# MLS01-TG000-C09.net
KiCad netlist of a schematic drawn in EAGLE
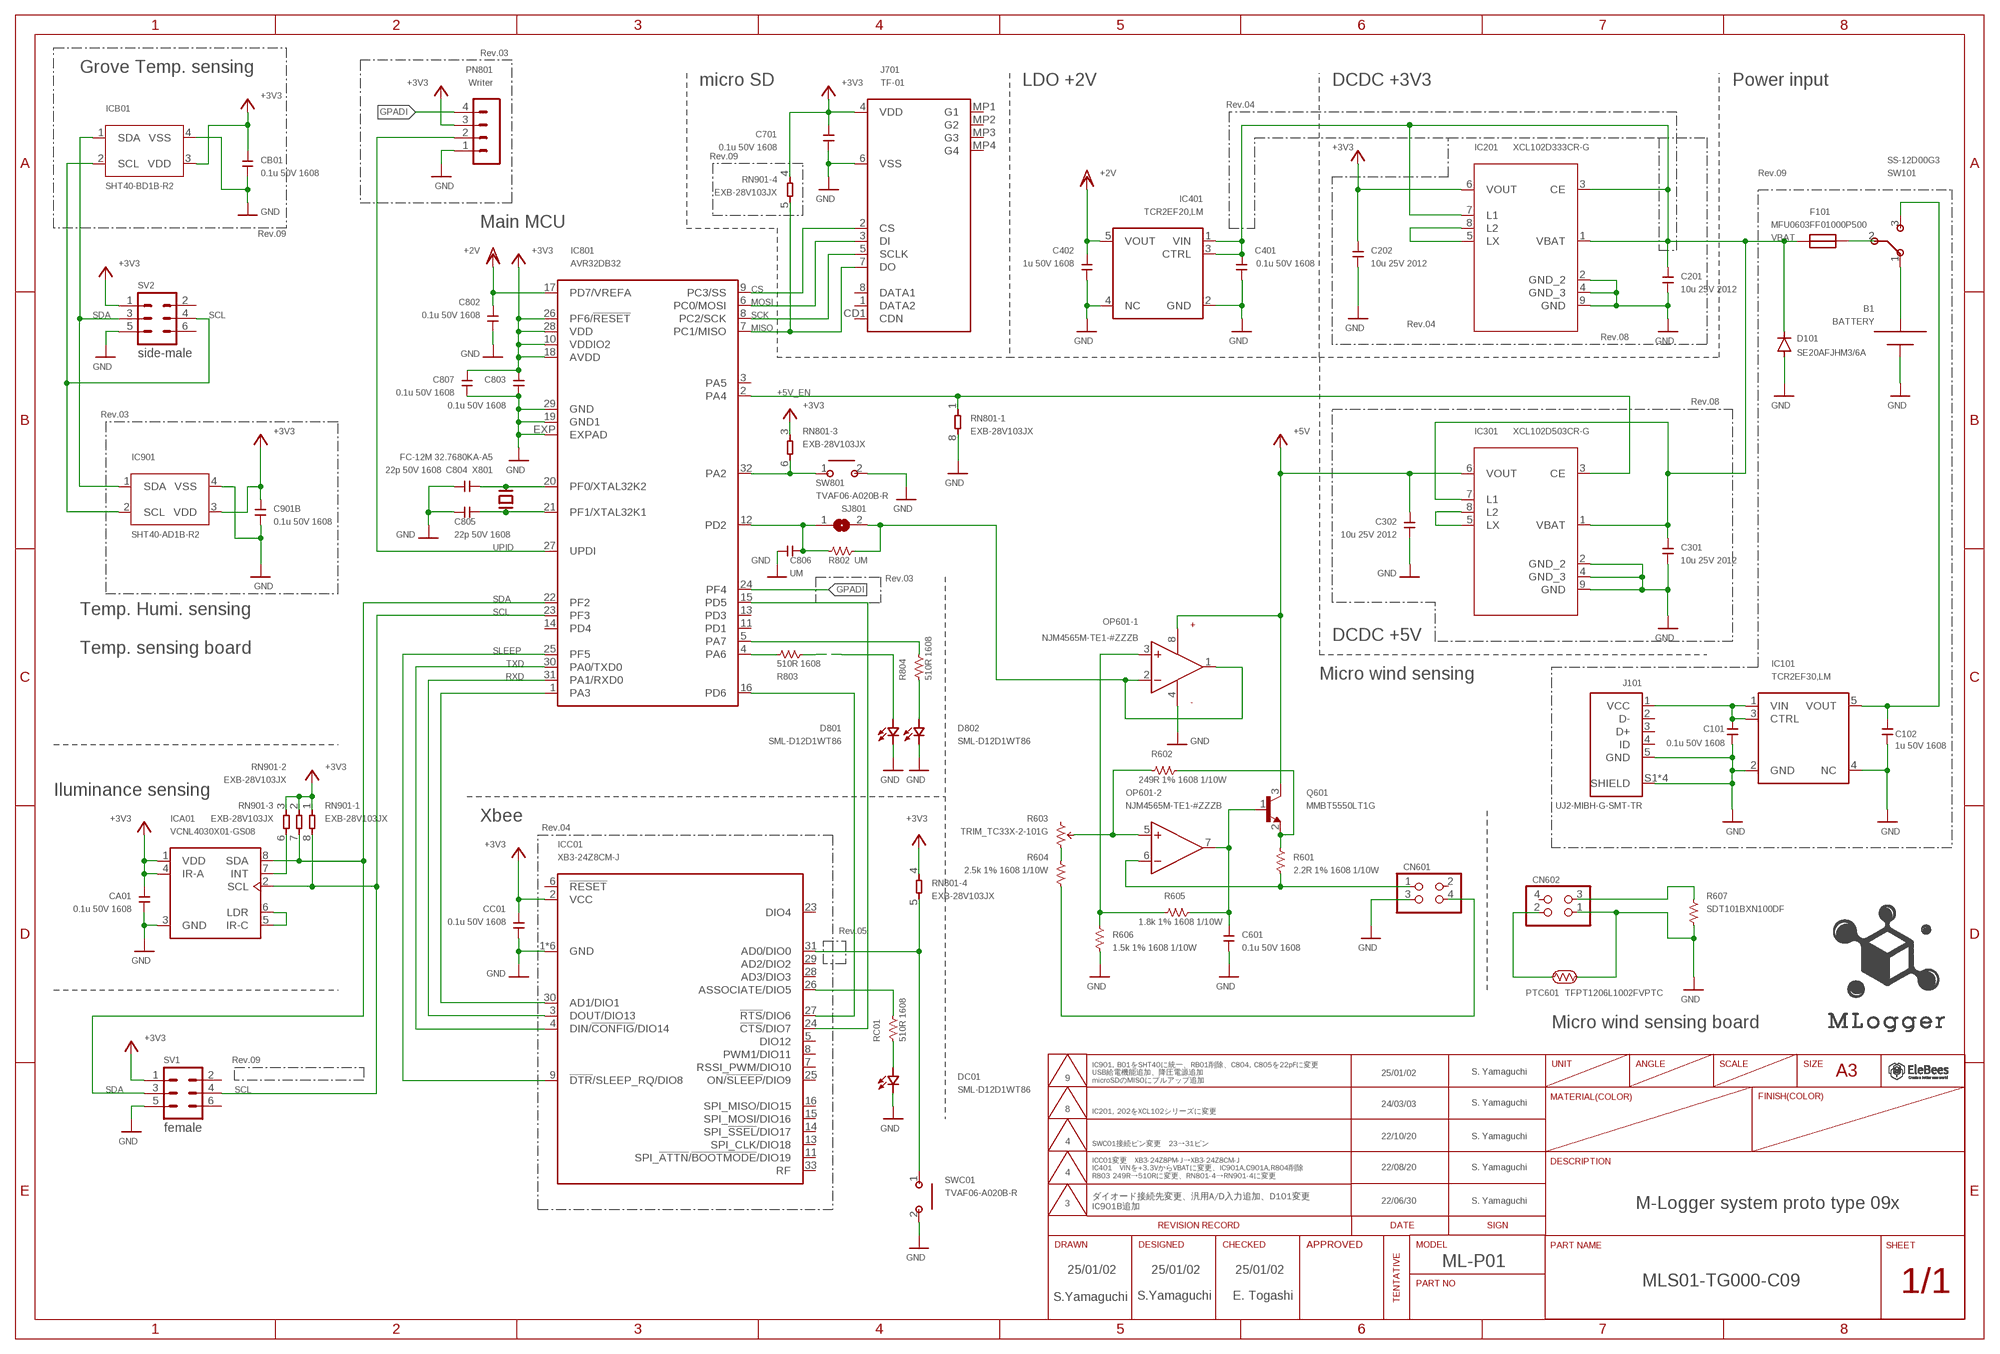
[diagram p0: schematic, sheet 1]

(export (version "E")
  (design (tool "Eeschema 10.0.6"))
  (components
    (comp (ref "B1")
      (value "BATTERY")
      (footprint "eagle-import:PAD")
      (libsource (lib "eagle-import") (part "BATTERY"))
    )
    (comp (ref "C101")
      (value "0.1u 50V 1608")
      (footprint "eagle-import:C-1608_0603")
      (libsource (lib "eagle-import") (part "CL10A105KP8NNNC"))
    )
    (comp (ref "C102")
      (value "1u 50V 1608")
      (footprint "eagle-import:C-1608_0603")
      (libsource (lib "eagle-import") (part "CL10A105KP8NNNC"))
    )
    (comp (ref "C201")
      (value "10u 25V 2012")
      (footprint "eagle-import:C-2012_0805")
      (libsource (lib "eagle-import") (part "CL21B105KBFNNNG"))
    )
    (comp (ref "C202")
      (value "10u 25V 2012")
      (footprint "eagle-import:C-2012_0805")
      (libsource (lib "eagle-import") (part "CL21B105KBFNNNG"))
    )
    (comp (ref "C301")
      (value "10u 25V 2012")
      (footprint "eagle-import:C-2012_0805")
      (libsource (lib "eagle-import") (part "CL21B105KBFNNNG"))
    )
    (comp (ref "C302")
      (value "10u 25V 2012")
      (footprint "eagle-import:C-2012_0805")
      (libsource (lib "eagle-import") (part "CL21B105KBFNNNG"))
    )
    (comp (ref "C401")
      (value "0.1u 50V 1608")
      (footprint "eagle-import:C-1608_0603")
      (libsource (lib "eagle-import") (part "CL10A105KP8NNNC"))
    )
    (comp (ref "C402")
      (value "1u 50V 1608")
      (footprint "eagle-import:C-1608_0603")
      (libsource (lib "eagle-import") (part "CL10A105KP8NNNC"))
    )
    (comp (ref "C601")
      (value "0.1u 50V 1608")
      (footprint "eagle-import:C-1608_0603")
      (libsource (lib "eagle-import") (part "CL10A105KP8NNNC"))
    )
    (comp (ref "C701")
      (value "0.1u 50V 1608")
      (footprint "eagle-import:C-1608_0603")
      (libsource (lib "eagle-import") (part "CL10A105KP8NNNC"))
    )
    (comp (ref "C802")
      (value "0.1u 50V 1608")
      (footprint "eagle-import:C-1608_0603")
      (libsource (lib "eagle-import") (part "CL10A105KP8NNNC"))
    )
    (comp (ref "C803")
      (value "0.1u 50V 1608")
      (footprint "eagle-import:C-1608_0603")
      (libsource (lib "eagle-import") (part "CL10A105KP8NNNC"))
    )
    (comp (ref "C804")
      (value "22p 50V 1608")
      (footprint "eagle-import:C-1608_0603")
      (libsource (lib "eagle-import") (part "CL10A105KP8NNNC"))
    )
    (comp (ref "C805")
      (value "22p 50V 1608")
      (footprint "eagle-import:C-1608_0603")
      (libsource (lib "eagle-import") (part "CL10A105KP8NNNC"))
    )
    (comp (ref "C806")
      (value "UM")
      (footprint "eagle-import:C-1608_0603")
      (libsource (lib "eagle-import") (part "CL10A105KP8NNNC"))
    )
    (comp (ref "C807")
      (value "0.1u 50V 1608")
      (footprint "eagle-import:C-1608_0603")
      (libsource (lib "eagle-import") (part "CL10A105KP8NNNC"))
    )
    (comp (ref "C901B")
      (value "0.1u 50V 1608")
      (footprint "eagle-import:C-1608_0603")
      (libsource (lib "eagle-import") (part "CL10A105KP8NNNC"))
    )
    (comp (ref "CA01")
      (value "0.1u 50V 1608")
      (footprint "eagle-import:C-1608_0603")
      (libsource (lib "eagle-import") (part "CL10A105KP8NNNC"))
    )
    (comp (ref "CB01")
      (value "0.1u 50V 1608")
      (footprint "eagle-import:C-1608_0603")
      (libsource (lib "eagle-import") (part "CL10A105KP8NNNC"))
    )
    (comp (ref "CC01")
      (value "0.1u 50V 1608")
      (footprint "eagle-import:C-1608_0603")
      (libsource (lib "eagle-import") (part "CL10A105KP8NNNC"))
    )
    (comp (ref "CN601")
      (value "PINHD-2X2")
      (footprint "eagle-import:2X02")
      (libsource (lib "eagle-import") (part "PINHD-2X2"))
    )
    (comp (ref "CN602")
      (value "PINHD-2X2")
      (footprint "eagle-import:2X02")
      (libsource (lib "eagle-import") (part "PINHD-2X2"))
    )
    (comp (ref "D101")
      (value "SE20AFJHM3/6A")
      (footprint "eagle-import:SODFL5629X125N")
      (libsource (lib "eagle-import") (part "GS2JFL-TP"))
    )
    (comp (ref "D801")
      (value "SML-D12D1WT86")
      (footprint "eagle-import:SMD-1608")
      (libsource (lib "eagle-import") (part "SML-D12D1WT86"))
    )
    (comp (ref "D802")
      (value "SML-D12D1WT86")
      (footprint "eagle-import:SMD-1608")
      (libsource (lib "eagle-import") (part "SML-D12D1WT86"))
    )
    (comp (ref "DC01")
      (value "SML-D12D1WT86")
      (footprint "eagle-import:SMD-1608")
      (libsource (lib "eagle-import") (part "SML-D12D1WT86"))
    )
    (comp (ref "F101")
      (value "MFU0603FF01000P500")
      (footprint "eagle-import:FUSC1608X60N")
      (libsource (lib "eagle-import") (part "MFU0603FF01000P500"))
    )
    (comp (ref "IC101")
      (value "TCR2EF30,LM")
      (footprint "eagle-import:SOT23-5L")
      (libsource (lib "eagle-import") (part "TCR2EF20,LM"))
    )
    (comp (ref "IC201")
      (value "XCL102D333CR-G")
      (footprint "eagle-import:CL-2025-02_TOR")
      (fields
        (field (name "MANUFACTURER_PART_NUMBER") "XCL102D503CR-G")
        (field (name "COPYRIGHT") "Copyright (C) 2021 Accelerated Designs. All rights reserved")
      )
      (libsource (lib "eagle-import") (part "XCL102D503CR-GCL-2025-02_TOR"))
    )
    (comp (ref "IC301")
      (value "XCL102D503CR-G")
      (footprint "eagle-import:CL-2025-02_TOR")
      (fields (field (name "COPYRIGHT") "Copyright (C) 2021 Accelerated Designs. All rights reserved"))
      (libsource (lib "eagle-import") (part "XCL102D503CR-GCL-2025-02_TOR"))
    )
    (comp (ref "IC401")
      (value "TCR2EF20,LM")
      (footprint "eagle-import:SOT23-5L")
      (libsource (lib "eagle-import") (part "TCR2EF20,LM"))
    )
    (comp (ref "IC801")
      (value "AVR32DB32")
      (footprint "eagle-import:HVQFN32")
      (libsource (lib "eagle-import") (part "AVR32DB32"))
    )
    (comp (ref "IC901")
      (value "SHT40-AD1B-R2")
      (footprint "eagle-import:SHT41")
      (libsource (lib "eagle-import") (part "SHT41"))
    )
    (comp (ref "ICA01")
      (value "VCNL4030X01-GS08")
      (footprint "eagle-import:VISHAY_VCNL4030X01-GS08")
      (fields (field (name "MF") "Vishay"))
      (libsource (lib "eagle-import") (part "VCNL4030X01-GS08"))
    )
    (comp (ref "ICB01")
      (value "SHT40-BD1B-R2")
      (footprint "eagle-import:SHT41")
      (libsource (lib "eagle-import") (part "SHT41"))
    )
    (comp (ref "ICC01")
      (value "XB3-24Z8CM-J")
      (footprint "eagle-import:XCVR_XB3-24Z8CM-J")
      (fields (field (name "MF") "Digi International"))
      (libsource (lib "eagle-import") (part "XB3-24Z8CM-J"))
    )
    (comp (ref "J101")
      (value "UJ2-MIBH-G-SMT-TR")
      (footprint "eagle-import:CUI_UJ2-MIBH-G-SMT-TR")
      (fields (field (name "MANUFACTURER") "CUI"))
      (libsource (lib "eagle-import") (part "UJ2-MIBH-G-SMT-TR"))
    )
    (comp (ref "J701")
      (value "TF-01")
      (footprint "eagle-import:TF-01A")
      (libsource (lib "eagle-import") (part "TF-01"))
    )
    (comp (ref "OP601")
      (value "NJM4565M-TE1-#ZZZB")
      (footprint "eagle-import:SOIC127P680X175-8N")
      (libsource (lib "eagle-import") (part "NJM4565M-TE1-#ZZZB"))
    )
    (comp (ref "PN801")
      (value "Writer")
      (footprint "eagle-import:MA04-1")
      (libsource (lib "eagle-import") (part "MA04-1"))
    )
    (comp (ref "PTC601")
      (value "TFPT1206L1002FVPTC")
      (footprint "eagle-import:C1206")
      (libsource (lib "eagle-import") (part "TFPT1206L1002FVPTC"))
    )
    (comp (ref "Q601")
      (value "MMBT5550LT1G")
      (footprint "eagle-import:SOT95P237X111-3N")
      (libsource (lib "eagle-import") (part "MMBT5550LT1G"))
    )
    (comp (ref "R601")
      (value "2.2R 1% 1608 1/10W")
      (footprint "eagle-import:R-1608_0603")
      (libsource (lib "eagle-import") (part "R-1608"))
    )
    (comp (ref "R602")
      (value "249R 1% 1608 1/10W")
      (footprint "eagle-import:R-1608_0603")
      (libsource (lib "eagle-import") (part "R-1608"))
    )
    (comp (ref "R603")
      (value "TRIM_TC33X-2-101G")
      (footprint "eagle-import:TRIM_TC33X-2-101G")
      (libsource (lib "eagle-import") (part "TRIM_TC33X-2-101G"))
    )
    (comp (ref "R604")
      (value "2.5k 1% 1608 1/10W")
      (footprint "eagle-import:R-1608_0603")
      (libsource (lib "eagle-import") (part "R-1608"))
    )
    (comp (ref "R605")
      (value "1.8k 1% 1608 1/10W")
      (footprint "eagle-import:R-1608_0603")
      (libsource (lib "eagle-import") (part "R-1608"))
    )
    (comp (ref "R606")
      (value "1.5k 1% 1608 1/10W")
      (footprint "eagle-import:R-1608_0603")
      (libsource (lib "eagle-import") (part "R-1608"))
    )
    (comp (ref "R607")
      (value "SDT101BXN100DF")
      (footprint "eagle-import:SDT101BXN100DF")
      (libsource (lib "eagle-import") (part "SDT101BXN100DF"))
    )
    (comp (ref "R802")
      (value "UM")
      (footprint "eagle-import:R-1608_0603")
      (libsource (lib "eagle-import") (part "R-1608"))
    )
    (comp (ref "R803")
      (value "510R 1608")
      (footprint "eagle-import:R-1608_0603")
      (libsource (lib "eagle-import") (part "R-1608"))
    )
    (comp (ref "R804")
      (value "510R 1608")
      (footprint "eagle-import:R-1608_0603")
      (libsource (lib "eagle-import") (part "R-1608"))
    )
    (comp (ref "RC01")
      (value "510R 1608")
      (footprint "eagle-import:R-1608_0603")
      (libsource (lib "eagle-import") (part "R-1608"))
    )
    (comp (ref "RN801")
      (value "EXB-28V103JX")
      (footprint "eagle-import:RESCAXS50P200X100X45-8N")
      (libsource (lib "eagle-import") (part "EXB-28V103JX"))
    )
    (comp (ref "RN901")
      (value "EXB-28V103JX")
      (footprint "eagle-import:RESCAXS50P200X100X45-8N")
      (libsource (lib "eagle-import") (part "EXB-28V103JX"))
    )
    (comp (ref "SJ801")
      (value "SJ")
      (footprint "eagle-import:SJ")
      (libsource (lib "eagle-import") (part "SJ"))
    )
    (comp (ref "SV1")
      (value "female")
      (footprint "eagle-import:MA03-2-FEMALE")
      (libsource (lib "eagle-import") (part "MA03-2-FEMALE"))
    )
    (comp (ref "SV2")
      (value "side-male")
      (footprint "eagle-import:MA03-2-SIDE-MALE")
      (libsource (lib "eagle-import") (part "MA03-2-SIDE-MALE"))
    )
    (comp (ref "SW101")
      (value "SS-12D00G3")
      (footprint "eagle-import:SS-12D00G3")
      (libsource (lib "eagle-import") (part "SS-12D00G3"))
    )
    (comp (ref "SW801")
      (value "TVAF06-A020B-R")
      (footprint "eagle-import:TVAF06-A020B-R")
      (libsource (lib "eagle-import") (part "TVAF06-A020B-R"))
    )
    (comp (ref "SWC01")
      (value "TVAF06-A020B-R")
      (footprint "eagle-import:TVAF06-A020B-R")
      (libsource (lib "eagle-import") (part "TVAF06-A020B-R"))
    )
    (comp (ref "U$4")
      (value "ELEBEES_SMALL")
      (footprint "eagle-import:ELEBEES_SMALL")
      (libsource (lib "eagle-import") (part "ELEBEES_SMALL"))
    )
    (comp (ref "X801")
      (value "FC-12M 32.7680KA-A5")
      (footprint "eagle-import:X2-SMD-L2.0X1.2X0.55MM")
      (fields (field (name "MF") "EPSON") (field (name "MP") "FC-12M"))
      (libsource (lib "eagle-import") (part "SMD-CRYSTAL-32.768KHZ-12.5PF-20PPM-90K(2P-L2.0X1.2MM)"))
    )
  )
  (nets
    (net (code "1") (name "+2V") (class "Default")
      (node (ref "C402") (pin "P$1") (pinfunction "1_P$1") (pintype "passive"))
      (node (ref "C802") (pin "P$1") (pinfunction "1_P$1") (pintype "passive"))
      (node (ref "IC401") (pin "5") (pinfunction "VOUT_5") (pintype "bidirectional"))
      (node (ref "IC801") (pin "17") (pinfunction "PD7/VREFA_17") (pintype "bidirectional"))
    )
    (net (code "2") (name "+3V3") (class "Default")
      (node (ref "C202") (pin "P$2") (pinfunction "2_P$2") (pintype "passive"))
      (node (ref "C701") (pin "P$1") (pinfunction "1_P$1") (pintype "passive"))
      (node (ref "C803") (pin "P$1") (pinfunction "1_P$1") (pintype "passive"))
      (node (ref "C807") (pin "P$1") (pinfunction "1_P$1") (pintype "passive"))
      (node (ref "C901B") (pin "P$1") (pinfunction "1_P$1") (pintype "passive"))
      (node (ref "CA01") (pin "P$1") (pinfunction "1_P$1") (pintype "passive"))
      (node (ref "CB01") (pin "P$1") (pinfunction "1_P$1") (pintype "passive"))
      (node (ref "CC01") (pin "P$1") (pinfunction "1_P$1") (pintype "passive"))
      (node (ref "IC201") (pin "6") (pinfunction "VOUT_6") (pintype "output"))
      (node (ref "IC801") (pin "10") (pinfunction "VDDIO2_10") (pintype "bidirectional"))
      (node (ref "IC801") (pin "18") (pinfunction "AVDD_18") (pintype "bidirectional"))
      (node (ref "IC801") (pin "26") (pinfunction "PF6/~{RESET}_26") (pintype "bidirectional"))
      (node (ref "IC801") (pin "28") (pinfunction "VDD_28") (pintype "bidirectional"))
      (node (ref "IC901") (pin "3") (pinfunction "VDD_3") (pintype "bidirectional"))
      (node (ref "ICA01") (pin "1") (pinfunction "VDD_1") (pintype "power_in"))
      (node (ref "ICA01") (pin "4") (pinfunction "IR-A_4") (pintype "input"))
      (node (ref "ICB01") (pin "3") (pinfunction "VDD_3") (pintype "bidirectional"))
      (node (ref "ICC01") (pin "2") (pinfunction "VCC_2") (pintype "power_in"))
      (node (ref "J701") (pin "4") (pinfunction "VDD_4") (pintype "bidirectional"))
      (node (ref "PN801") (pin "3") (pinfunction "3_3") (pintype "passive"))
      (node (ref "RN801") (pin "3") (pinfunction "1_3") (pintype "passive"))
      (node (ref "RN801") (pin "4") (pinfunction "1_4") (pintype "passive"))
      (node (ref "RN901") (pin "1") (pinfunction "1_1") (pintype "passive"))
      (node (ref "RN901") (pin "2") (pinfunction "1_2") (pintype "passive"))
      (node (ref "RN901") (pin "3") (pinfunction "1_3") (pintype "passive"))
      (node (ref "RN901") (pin "4") (pinfunction "1_4") (pintype "passive"))
      (node (ref "SV1") (pin "1") (pinfunction "1_1") (pintype "passive"))
      (node (ref "SV2") (pin "1") (pinfunction "1_1") (pintype "passive"))
    )
    (net (code "3") (name "+5V") (class "Default")
      (node (ref "C302") (pin "P$2") (pinfunction "2_P$2") (pintype "passive"))
      (node (ref "IC301") (pin "6") (pinfunction "VOUT_6") (pintype "output"))
      (node (ref "OP601") (pin "8") (pinfunction "V+_8") (pintype "power_in"))
      (node (ref "Q601") (pin "3") (pinfunction "C_3") (pintype "passive"))
    )
    (net (code "4") (name "/+5V_EN") (class "Default")
      (node (ref "IC301") (pin "3") (pinfunction "CE_3") (pintype "input"))
      (node (ref "IC801") (pin "2") (pinfunction "PA4_2") (pintype "bidirectional"))
      (node (ref "RN801") (pin "1") (pinfunction "1_1") (pintype "passive"))
    )
    (net (code "5") (name "/CS") (class "Default")
      (node (ref "IC801") (pin "9") (pinfunction "PC3/SS_9") (pintype "bidirectional"))
      (node (ref "J701") (pin "2") (pinfunction "CS_2") (pintype "bidirectional"))
    )
    (net (code "6") (name "/MISO") (class "Default")
      (node (ref "IC801") (pin "7") (pinfunction "PC1/MISO_7") (pintype "bidirectional"))
      (node (ref "J701") (pin "7") (pinfunction "DO_7") (pintype "bidirectional"))
      (node (ref "RN901") (pin "5") (pinfunction "2_5") (pintype "passive"))
    )
    (net (code "7") (name "/MOSI") (class "Default")
      (node (ref "IC801") (pin "6") (pinfunction "PC0/MOSI_6") (pintype "bidirectional"))
      (node (ref "J701") (pin "3") (pinfunction "DI_3") (pintype "bidirectional"))
    )
    (net (code "8") (name "/N$3") (class "Default")
      (node (ref "CN601") (pin "4") (pinfunction "4_4") (pintype "passive"))
      (node (ref "CN602") (pin "2") (pinfunction "2_2") (pintype "passive"))
      (node (ref "PTC601") (pin "2") (pinfunction "2_2") (pintype "passive"))
      (node (ref "R604") (pin "1") (pinfunction "1_1") (pintype "passive"))
    )
    (net (code "9") (name "/N$20") (class "Default")
      (node (ref "CN601") (pin "1") (pinfunction "1_1") (pintype "passive"))
      (node (ref "CN602") (pin "3") (pinfunction "3_3") (pintype "passive"))
      (node (ref "OP601") (pin "6") (pinfunction "-IN_6") (pintype "input"))
      (node (ref "R601") (pin "1") (pinfunction "1_1") (pintype "passive"))
      (node (ref "R607") (pin "2") (pinfunction "2_2") (pintype "passive"))
    )
    (net (code "10") (name "/RXD") (class "Default")
      (node (ref "IC801") (pin "31") (pinfunction "PA1/RXD0_31") (pintype "bidirectional"))
      (node (ref "ICC01") (pin "3") (pinfunction "DOUT/DIO13_3") (pintype "bidirectional"))
    )
    (net (code "11") (name "/SCK") (class "Default")
      (node (ref "IC801") (pin "8") (pinfunction "PC2/SCK_8") (pintype "bidirectional"))
      (node (ref "J701") (pin "5") (pinfunction "SCLK_5") (pintype "bidirectional"))
    )
    (net (code "12") (name "/SCL") (class "Default")
      (node (ref "IC801") (pin "23") (pinfunction "PF3_23") (pintype "bidirectional"))
      (node (ref "IC901") (pin "2") (pinfunction "SCL_2") (pintype "bidirectional"))
      (node (ref "ICA01") (pin "2") (pinfunction "SCL_2") (pintype "input"))
      (node (ref "ICB01") (pin "2") (pinfunction "SCL_2") (pintype "bidirectional"))
      (node (ref "RN901") (pin "8") (pinfunction "2_8") (pintype "passive"))
      (node (ref "SV1") (pin "4") (pinfunction "4_4") (pintype "passive"))
      (node (ref "SV2") (pin "4") (pinfunction "4_4") (pintype "passive"))
    )
    (net (code "13") (name "/SDA") (class "Default")
      (node (ref "IC801") (pin "22") (pinfunction "PF2_22") (pintype "bidirectional"))
      (node (ref "IC901") (pin "1") (pinfunction "SDA_1") (pintype "bidirectional"))
      (node (ref "ICA01") (pin "8") (pinfunction "SDA_8") (pintype "bidirectional"))
      (node (ref "ICB01") (pin "1") (pinfunction "SDA_1") (pintype "bidirectional"))
      (node (ref "RN901") (pin "7") (pinfunction "2_7") (pintype "passive"))
      (node (ref "SV1") (pin "3") (pinfunction "3_3") (pintype "passive"))
      (node (ref "SV2") (pin "3") (pinfunction "3_3") (pintype "passive"))
    )
    (net (code "14") (name "/SLEEP") (class "Default")
      (node (ref "IC801") (pin "25") (pinfunction "PF5_25") (pintype "bidirectional"))
      (node (ref "ICC01") (pin "9") (pinfunction "~{DTR}/SLEEP_RQ/DIO8_9") (pintype "bidirectional"))
    )
    (net (code "15") (name "/TXD") (class "Default")
      (node (ref "IC801") (pin "30") (pinfunction "PA0/TXD0_30") (pintype "bidirectional"))
      (node (ref "ICC01") (pin "4") (pinfunction "DIN/~{CONFIG}/DIO14_4") (pintype "bidirectional"))
    )
    (net (code "16") (name "/UPID") (class "Default")
      (node (ref "IC801") (pin "27") (pinfunction "UPDI_27") (pintype "bidirectional"))
      (node (ref "PN801") (pin "2") (pinfunction "2_2") (pintype "passive"))
    )
    (net (code "17") (name "/VBAT") (class "Default")
      (node (ref "C201") (pin "P$2") (pinfunction "2_P$2") (pintype "passive"))
      (node (ref "C301") (pin "P$2") (pinfunction "2_P$2") (pintype "passive"))
      (node (ref "C401") (pin "P$1") (pinfunction "1_P$1") (pintype "passive"))
      (node (ref "D101") (pin "1") (pinfunction "C_1") (pintype "passive"))
      (node (ref "F101") (pin "2") (pinfunction "2_2") (pintype "bidirectional"))
      (node (ref "IC201") (pin "1") (pinfunction "VBAT_1") (pintype "power_in"))
      (node (ref "IC201") (pin "3") (pinfunction "CE_3") (pintype "input"))
      (node (ref "IC201") (pin "7") (pinfunction "L1_7") (pintype "bidirectional"))
      (node (ref "IC301") (pin "1") (pinfunction "VBAT_1") (pintype "power_in"))
      (node (ref "IC301") (pin "7") (pinfunction "L1_7") (pintype "bidirectional"))
      (node (ref "IC401") (pin "1") (pinfunction "VIN_1") (pintype "bidirectional"))
      (node (ref "IC401") (pin "3") (pinfunction "CTRL_3") (pintype "bidirectional"))
    )
    (net (code "18") (name "GND") (class "Default")
      (node (ref "B1") (pin "2") (pinfunction "-_2") (pintype "bidirectional"))
      (node (ref "C101") (pin "P$2") (pinfunction "2_P$2") (pintype "passive"))
      (node (ref "C102") (pin "P$2") (pinfunction "2_P$2") (pintype "passive"))
      (node (ref "C201") (pin "P$1") (pinfunction "1_P$1") (pintype "passive"))
      (node (ref "C202") (pin "P$1") (pinfunction "1_P$1") (pintype "passive"))
      (node (ref "C301") (pin "P$1") (pinfunction "1_P$1") (pintype "passive"))
      (node (ref "C302") (pin "P$1") (pinfunction "1_P$1") (pintype "passive"))
      (node (ref "C401") (pin "P$2") (pinfunction "2_P$2") (pintype "passive"))
      (node (ref "C402") (pin "P$2") (pinfunction "2_P$2") (pintype "passive"))
      (node (ref "C601") (pin "P$2") (pinfunction "2_P$2") (pintype "passive"))
      (node (ref "C701") (pin "P$2") (pinfunction "2_P$2") (pintype "passive"))
      (node (ref "C802") (pin "P$2") (pinfunction "2_P$2") (pintype "passive"))
      (node (ref "C803") (pin "P$2") (pinfunction "2_P$2") (pintype "passive"))
      (node (ref "C804") (pin "P$2") (pinfunction "2_P$2") (pintype "passive"))
      (node (ref "C805") (pin "P$2") (pinfunction "2_P$2") (pintype "passive"))
      (node (ref "C806") (pin "P$2") (pinfunction "2_P$2") (pintype "passive"))
      (node (ref "C807") (pin "P$2") (pinfunction "2_P$2") (pintype "passive"))
      (node (ref "C901B") (pin "P$2") (pinfunction "2_P$2") (pintype "passive"))
      (node (ref "CA01") (pin "P$2") (pinfunction "2_P$2") (pintype "passive"))
      (node (ref "CB01") (pin "P$2") (pinfunction "2_P$2") (pintype "passive"))
      (node (ref "CC01") (pin "P$2") (pinfunction "2_P$2") (pintype "passive"))
      (node (ref "CN601") (pin "3") (pinfunction "3_3") (pintype "passive"))
      (node (ref "CN602") (pin "1") (pinfunction "1_1") (pintype "passive"))
      (node (ref "D101") (pin "2") (pinfunction "A_2") (pintype "passive"))
      (node (ref "D801") (pin "2") (pinfunction "C_2") (pintype "passive"))
      (node (ref "D802") (pin "2") (pinfunction "C_2") (pintype "passive"))
      (node (ref "DC01") (pin "2") (pinfunction "C_2") (pintype "passive"))
      (node (ref "IC101") (pin "2") (pinfunction "GND_2") (pintype "bidirectional"))
      (node (ref "IC101") (pin "4") (pinfunction "NC_4") (pintype "bidirectional"))
      (node (ref "IC201") (pin "2") (pinfunction "GND_2_2") (pintype "passive"))
      (node (ref "IC201") (pin "4") (pinfunction "GND_3_4") (pintype "passive"))
      (node (ref "IC201") (pin "9") (pinfunction "GND_9") (pintype "passive"))
      (node (ref "IC301") (pin "2") (pinfunction "GND_2_2") (pintype "passive"))
      (node (ref "IC301") (pin "4") (pinfunction "GND_3_4") (pintype "passive"))
      (node (ref "IC301") (pin "9") (pinfunction "GND_9") (pintype "passive"))
      (node (ref "IC401") (pin "2") (pinfunction "GND_2") (pintype "bidirectional"))
      (node (ref "IC401") (pin "4") (pinfunction "NC_4") (pintype "bidirectional"))
      (node (ref "IC801") (pin "19") (pinfunction "GND1_19") (pintype "bidirectional"))
      (node (ref "IC801") (pin "29") (pinfunction "GND_29") (pintype "bidirectional"))
      (node (ref "IC801") (pin "EXP") (pinfunction "EXPAD_EXP") (pintype "bidirectional"))
      (node (ref "IC901") (pin "4") (pinfunction "VSS_4") (pintype "bidirectional"))
      (node (ref "ICA01") (pin "3") (pinfunction "GND_3") (pintype "power_in"))
      (node (ref "ICB01") (pin "4") (pinfunction "VSS_4") (pintype "bidirectional"))
      (node (ref "ICC01") (pin "1") (pinfunction "GND_1") (pintype "power_in"))
      (node (ref "ICC01") (pin "10") (pinfunction "GND_10") (pintype "power_in"))
      (node (ref "ICC01") (pin "12") (pinfunction "GND_12") (pintype "power_in"))
      (node (ref "ICC01") (pin "21") (pinfunction "GND_21") (pintype "power_in"))
      (node (ref "ICC01") (pin "32") (pinfunction "GND_32") (pintype "power_in"))
      (node (ref "ICC01") (pin "34") (pinfunction "GND_34") (pintype "power_in"))
      (node (ref "J101") (pin "5") (pinfunction "GND_5") (pintype "power_in"))
      (node (ref "J101") (pin "S1") (pinfunction "SHIELD_S1") (pintype "passive"))
      (node (ref "J101") (pin "S2") (pinfunction "SHIELD_S2") (pintype "passive"))
      (node (ref "J101") (pin "S3") (pinfunction "SHIELD_S3") (pintype "passive"))
      (node (ref "J101") (pin "S4") (pinfunction "SHIELD_S4") (pintype "passive"))
      (node (ref "J701") (pin "6") (pinfunction "VSS_6") (pintype "bidirectional"))
      (node (ref "OP601") (pin "4") (pinfunction "V-_4") (pintype "power_in"))
      (node (ref "PN801") (pin "1") (pinfunction "1_1") (pintype "passive"))
      (node (ref "PTC601") (pin "1") (pinfunction "1_1") (pintype "passive"))
      (node (ref "R606") (pin "1") (pinfunction "1_1") (pintype "passive"))
      (node (ref "R607") (pin "1") (pinfunction "1_1") (pintype "passive"))
      (node (ref "RN801") (pin "8") (pinfunction "2_8") (pintype "passive"))
      (node (ref "SV1") (pin "5") (pinfunction "5_5") (pintype "passive"))
      (node (ref "SV2") (pin "5") (pinfunction "5_5") (pintype "passive"))
      (node (ref "SW801") (pin "2") (pinfunction "2_2") (pintype "bidirectional"))
      (node (ref "SWC01") (pin "2") (pinfunction "2_2") (pintype "bidirectional"))
    )
    (net (code "19") (name "GPADI") (class "Default")
      (node (ref "IC801") (pin "24") (pinfunction "PF4_24") (pintype "bidirectional"))
      (node (ref "PN801") (pin "4") (pinfunction "4_4") (pintype "passive"))
    )
    (net (code "20") (name "Net-(B1-+)") (class "Default")
      (node (ref "B1") (pin "1") (pinfunction "+_1") (pintype "bidirectional"))
      (node (ref "SW101") (pin "1") (pinfunction "1_1") (pintype "bidirectional"))
    )
    (net (code "21") (name "Net-(C101-1)") (class "Default")
      (node (ref "C101") (pin "P$1") (pinfunction "1_P$1") (pintype "passive"))
      (node (ref "IC101") (pin "1") (pinfunction "VIN_1") (pintype "bidirectional"))
      (node (ref "IC101") (pin "3") (pinfunction "CTRL_3") (pintype "bidirectional"))
      (node (ref "J101") (pin "1") (pinfunction "VCC_1") (pintype "power_in"))
    )
    (net (code "22") (name "Net-(C102-1)") (class "Default")
      (node (ref "C102") (pin "P$1") (pinfunction "1_P$1") (pintype "passive"))
      (node (ref "IC101") (pin "5") (pinfunction "VOUT_5") (pintype "bidirectional"))
      (node (ref "SW101") (pin "3") (pinfunction "2_3") (pintype "bidirectional"))
    )
    (net (code "23") (name "Net-(C601-1)") (class "Default")
      (node (ref "C601") (pin "P$1") (pinfunction "1_P$1") (pintype "passive"))
      (node (ref "OP601") (pin "7") (pinfunction "OUT_7") (pintype "output"))
      (node (ref "Q601") (pin "1") (pinfunction "B_1") (pintype "passive"))
      (node (ref "R605") (pin "2") (pinfunction "2_2") (pintype "passive"))
    )
    (net (code "24") (name "Net-(C804-1)") (class "Default")
      (node (ref "C804") (pin "P$1") (pinfunction "1_P$1") (pintype "passive"))
      (node (ref "IC801") (pin "20") (pinfunction "PF0/XTAL32K2_20") (pintype "bidirectional"))
      (node (ref "X801") (pin "1") (pinfunction "1_1") (pintype "passive"))
    )
    (net (code "25") (name "Net-(C805-1)") (class "Default")
      (node (ref "C805") (pin "P$1") (pinfunction "1_P$1") (pintype "passive"))
      (node (ref "IC801") (pin "21") (pinfunction "PF1/XTAL32K1_21") (pintype "bidirectional"))
      (node (ref "X801") (pin "2") (pinfunction "2_2") (pintype "passive"))
    )
    (net (code "26") (name "Net-(C806-1)") (class "Default")
      (node (ref "C806") (pin "P$1") (pinfunction "1_P$1") (pintype "passive"))
      (node (ref "IC801") (pin "12") (pinfunction "PD2_12") (pintype "bidirectional"))
      (node (ref "R802") (pin "1") (pinfunction "1_1") (pintype "passive"))
      (node (ref "SJ801") (pin "1") (pinfunction "1_1") (pintype "passive"))
    )
    (net (code "27") (name "Net-(D801-A)") (class "Default")
      (node (ref "D801") (pin "1") (pinfunction "A_1") (pintype "passive"))
      (node (ref "R803") (pin "2") (pinfunction "2_2") (pintype "passive"))
    )
    (net (code "28") (name "Net-(D802-A)") (class "Default")
      (node (ref "D802") (pin "1") (pinfunction "A_1") (pintype "passive"))
      (node (ref "R804") (pin "1") (pinfunction "1_1") (pintype "passive"))
    )
    (net (code "29") (name "Net-(DC01-A)") (class "Default")
      (node (ref "DC01") (pin "1") (pinfunction "A_1") (pintype "passive"))
      (node (ref "RC01") (pin "1") (pinfunction "1_1") (pintype "passive"))
    )
    (net (code "30") (name "Net-(IC201-L2)") (class "Default")
      (node (ref "IC201") (pin "5") (pinfunction "LX_5") (pintype "passive"))
      (node (ref "IC201") (pin "8") (pinfunction "L2_8") (pintype "bidirectional"))
    )
    (net (code "31") (name "Net-(IC301-L2)") (class "Default")
      (node (ref "IC301") (pin "5") (pinfunction "LX_5") (pintype "passive"))
      (node (ref "IC301") (pin "8") (pinfunction "L2_8") (pintype "bidirectional"))
    )
    (net (code "32") (name "Net-(IC801-PA2)") (class "Default")
      (node (ref "IC801") (pin "32") (pinfunction "PA2_32") (pintype "bidirectional"))
      (node (ref "RN801") (pin "6") (pinfunction "2_6") (pintype "passive"))
      (node (ref "SW801") (pin "1") (pinfunction "1_1") (pintype "bidirectional"))
    )
    (net (code "33") (name "Net-(IC801-PA3)") (class "Default")
      (node (ref "IC801") (pin "1") (pinfunction "PA3_1") (pintype "bidirectional"))
      (node (ref "ICC01") (pin "30") (pinfunction "AD1/DIO1_30") (pintype "bidirectional"))
    )
    (net (code "34") (name "Net-(IC801-PA6)") (class "Default")
      (node (ref "IC801") (pin "4") (pinfunction "PA6_4") (pintype "bidirectional"))
      (node (ref "R803") (pin "1") (pinfunction "1_1") (pintype "passive"))
    )
    (net (code "35") (name "Net-(IC801-PA7)") (class "Default")
      (node (ref "IC801") (pin "5") (pinfunction "PA7_5") (pintype "bidirectional"))
      (node (ref "R804") (pin "2") (pinfunction "2_2") (pintype "passive"))
    )
    (net (code "36") (name "Net-(IC801-PD5)") (class "Default")
      (node (ref "IC801") (pin "15") (pinfunction "PD5_15") (pintype "bidirectional"))
      (node (ref "ICC01") (pin "24") (pinfunction "~{CTS}/DIO7_24") (pintype "bidirectional"))
    )
    (net (code "37") (name "Net-(IC801-PD6)") (class "Default")
      (node (ref "IC801") (pin "16") (pinfunction "PD6_16") (pintype "bidirectional"))
      (node (ref "ICC01") (pin "27") (pinfunction "~{RTS}/DIO6_27") (pintype "bidirectional"))
    )
    (net (code "38") (name "Net-(ICA01-INT)") (class "Default")
      (node (ref "ICA01") (pin "7") (pinfunction "INT_7") (pintype "bidirectional"))
      (node (ref "RN901") (pin "6") (pinfunction "2_6") (pintype "passive"))
    )
    (net (code "39") (name "Net-(ICA01-IR-C)") (class "Default")
      (node (ref "ICA01") (pin "5") (pinfunction "IR-C_5") (pintype "output"))
      (node (ref "ICA01") (pin "6") (pinfunction "LDR_6") (pintype "bidirectional"))
    )
    (net (code "40") (name "Net-(ICC01-AD0{slash}DIO0)") (class "Default")
      (node (ref "ICC01") (pin "31") (pinfunction "AD0/DIO0_31") (pintype "bidirectional"))
      (node (ref "RN801") (pin "5") (pinfunction "2_5") (pintype "passive"))
      (node (ref "SWC01") (pin "1") (pinfunction "1_1") (pintype "bidirectional"))
    )
    (net (code "41") (name "Net-(ICC01-ASSOCIATE{slash}DIO5)") (class "Default")
      (node (ref "ICC01") (pin "26") (pinfunction "ASSOCIATE/DIO5_26") (pintype "bidirectional"))
      (node (ref "RC01") (pin "2") (pinfunction "2_2") (pintype "passive"))
    )
    (net (code "42") (name "Net-(OP601A-+IN)") (class "Default")
      (node (ref "OP601") (pin "3") (pinfunction "+IN_3") (pintype "input"))
      (node (ref "R605") (pin "1") (pinfunction "1_1") (pintype "passive"))
      (node (ref "R606") (pin "2") (pinfunction "2_2") (pintype "passive"))
    )
    (net (code "43") (name "Net-(OP601A--IN)") (class "Default")
      (node (ref "OP601") (pin "1") (pinfunction "OUT_1") (pintype "output"))
      (node (ref "OP601") (pin "2") (pinfunction "-IN_2") (pintype "input"))
      (node (ref "R802") (pin "2") (pinfunction "2_2") (pintype "passive"))
      (node (ref "SJ801") (pin "2") (pinfunction "2_2") (pintype "passive"))
    )
    (net (code "44") (name "Net-(OP601B-+IN)") (class "Default")
      (node (ref "OP601") (pin "5") (pinfunction "+IN_5") (pintype "input"))
      (node (ref "R602") (pin "1") (pinfunction "1_1") (pintype "passive"))
      (node (ref "R603") (pin "2") (pinfunction "2_2") (pintype "bidirectional"))
    )
    (net (code "45") (name "Net-(Q601-E)") (class "Default")
      (node (ref "Q601") (pin "2") (pinfunction "E_2") (pintype "passive"))
      (node (ref "R601") (pin "2") (pinfunction "2_2") (pintype "passive"))
      (node (ref "R602") (pin "2") (pinfunction "2_2") (pintype "passive"))
    )
    (net (code "46") (name "Net-(R603-Pad3)") (class "Default")
      (node (ref "R603") (pin "3") (pinfunction "3_3") (pintype "passive"))
      (node (ref "R604") (pin "2") (pinfunction "2_2") (pintype "passive"))
    )
    (net (code "47") (name "Net-(SW101-P$1)") (class "Default")
      (node (ref "F101") (pin "1") (pinfunction "1_1") (pintype "bidirectional"))
      (node (ref "SW101") (pin "2") (pinfunction "P$1_2") (pintype "bidirectional"))
    )
    (net (code "48") (name "unconnected-(CN601-Pad2)") (class "Default")
      (node (ref "CN601") (pin "2") (pinfunction "2_2") (pintype "passive"))
    )
    (net (code "49") (name "unconnected-(CN602-Pad4)") (class "Default")
      (node (ref "CN602") (pin "4") (pinfunction "4_4") (pintype "passive"))
    )
    (net (code "50") (name "unconnected-(IC801-PA5-Pad3)") (class "Default")
      (node (ref "IC801") (pin "3") (pinfunction "PA5_3") (pintype "bidirectional"))
    )
    (net (code "51") (name "unconnected-(IC801-PD1-Pad11)") (class "Default")
      (node (ref "IC801") (pin "11") (pinfunction "PD1_11") (pintype "bidirectional"))
    )
    (net (code "52") (name "unconnected-(IC801-PD3-Pad13)") (class "Default")
      (node (ref "IC801") (pin "13") (pinfunction "PD3_13") (pintype "bidirectional"))
    )
    (net (code "53") (name "unconnected-(IC801-PD4-Pad14)") (class "Default")
      (node (ref "IC801") (pin "14") (pinfunction "PD4_14") (pintype "bidirectional"))
    )
    (net (code "54") (name "unconnected-(ICC01-AD2{slash}DIO2-Pad29)") (class "Default")
      (node (ref "ICC01") (pin "29") (pinfunction "AD2/DIO2_29") (pintype "bidirectional"))
    )
    (net (code "55") (name "unconnected-(ICC01-AD3{slash}DIO3-Pad28)") (class "Default")
      (node (ref "ICC01") (pin "28") (pinfunction "AD3/DIO3_28") (pintype "bidirectional"))
    )
    (net (code "56") (name "unconnected-(ICC01-DIO4-Pad23)") (class "Default")
      (node (ref "ICC01") (pin "23") (pinfunction "DIO4_23") (pintype "bidirectional"))
    )
    (net (code "57") (name "unconnected-(ICC01-DIO12-Pad5)") (class "Default")
      (node (ref "ICC01") (pin "5") (pinfunction "DIO12_5") (pintype "bidirectional"))
    )
    (net (code "58") (name "unconnected-(ICC01-ON{slash}~{SLEEP}{slash}DIO9-Pad25)") (class "Default")
      (node (ref "ICC01") (pin "25") (pinfunction "ON/~{SLEEP}/DIO9_25") (pintype "bidirectional"))
    )
    (net (code "59") (name "unconnected-(ICC01-PWM1{slash}DIO11-Pad8)") (class "Default")
      (node (ref "ICC01") (pin "8") (pinfunction "PWM1/DIO11_8") (pintype "bidirectional"))
    )
    (net (code "60") (name "unconnected-(ICC01-RF-Pad33)") (class "Default")
      (node (ref "ICC01") (pin "33") (pinfunction "RF_33") (pintype "bidirectional"))
    )
    (net (code "61") (name "unconnected-(ICC01-RSSI_PWM{slash}DIO10-Pad7)") (class "Default")
      (node (ref "ICC01") (pin "7") (pinfunction "RSSI_PWM/DIO10_7") (pintype "bidirectional"))
    )
    (net (code "62") (name "unconnected-(ICC01-SPI_CLK{slash}DIO18-Pad13)") (class "Default")
      (node (ref "ICC01") (pin "13") (pinfunction "SPI_CLK/DIO18_13") (pintype "bidirectional"))
    )
    (net (code "63") (name "unconnected-(ICC01-SPI_MISO{slash}DIO15-Pad16)") (class "Default")
      (node (ref "ICC01") (pin "16") (pinfunction "SPI_MISO/DIO15_16") (pintype "bidirectional"))
    )
    (net (code "64") (name "unconnected-(ICC01-SPI_MOSI{slash}DIO16-Pad15)") (class "Default")
      (node (ref "ICC01") (pin "15") (pinfunction "SPI_MOSI/DIO16_15") (pintype "bidirectional"))
    )
    (net (code "65") (name "unconnected-(ICC01-SPI_~{ATTN}{slash}~{BOOTMODE}{slash}DIO19-Pad11)") (class "Default")
      (node (ref "ICC01") (pin "11") (pinfunction "SPI_~{ATTN}/~{BOOTMODE}/DIO19_11") (pintype "bidirectional"))
    )
    (net (code "66") (name "unconnected-(ICC01-SPI_~{SSEL}{slash}DIO17-Pad14)") (class "Default")
      (node (ref "ICC01") (pin "14") (pinfunction "SPI_~{SSEL}/DIO17_14") (pintype "bidirectional"))
    )
    (net (code "67") (name "unconnected-(ICC01-~{RESET}-Pad6)") (class "Default")
      (node (ref "ICC01") (pin "6") (pinfunction "~{RESET}_6") (pintype "input"))
    )
    (net (code "68") (name "unconnected-(J101-D+-Pad3)") (class "Default")
      (node (ref "J101") (pin "3") (pinfunction "D+_3") (pintype "bidirectional"))
    )
    (net (code "69") (name "unconnected-(J101-D--Pad2)") (class "Default")
      (node (ref "J101") (pin "2") (pinfunction "D-_2") (pintype "bidirectional"))
    )
    (net (code "70") (name "unconnected-(J101-ID-Pad4)") (class "Default")
      (node (ref "J101") (pin "4") (pinfunction "ID_4") (pintype "bidirectional"))
    )
    (net (code "71") (name "unconnected-(J701-CDN-PadCD1)") (class "Default")
      (node (ref "J701") (pin "CD1") (pinfunction "CDN_CD1") (pintype "bidirectional"))
    )
    (net (code "72") (name "unconnected-(J701-DATA1-Pad8)") (class "Default")
      (node (ref "J701") (pin "8") (pinfunction "DATA1_8") (pintype "bidirectional"))
    )
    (net (code "73") (name "unconnected-(J701-DATA2-Pad1)") (class "Default")
      (node (ref "J701") (pin "1") (pinfunction "DATA2_1") (pintype "bidirectional"))
    )
    (net (code "74") (name "unconnected-(J701-G1-PadMP1)") (class "Default")
      (node (ref "J701") (pin "MP1") (pinfunction "G1_MP1") (pintype "bidirectional"))
    )
    (net (code "75") (name "unconnected-(J701-G2-PadMP2)") (class "Default")
      (node (ref "J701") (pin "MP2") (pinfunction "G2_MP2") (pintype "bidirectional"))
    )
    (net (code "76") (name "unconnected-(J701-G3-PadMP3)") (class "Default")
      (node (ref "J701") (pin "MP3") (pinfunction "G3_MP3") (pintype "bidirectional"))
    )
    (net (code "77") (name "unconnected-(J701-G4-PadMP4)") (class "Default")
      (node (ref "J701") (pin "MP4") (pinfunction "G4_MP4") (pintype "bidirectional"))
    )
    (net (code "78") (name "unconnected-(R603-Pad1)") (class "Default")
      (node (ref "R603") (pin "1") (pinfunction "1_1") (pintype "passive"))
    )
    (net (code "79") (name "unconnected-(SV1-Pad2)") (class "Default")
      (node (ref "SV1") (pin "2") (pinfunction "2_2") (pintype "passive"))
    )
    (net (code "80") (name "unconnected-(SV1-Pad6)") (class "Default")
      (node (ref "SV1") (pin "6") (pinfunction "6_6") (pintype "passive"))
    )
    (net (code "81") (name "unconnected-(SV2-Pad2)") (class "Default")
      (node (ref "SV2") (pin "2") (pinfunction "2_2") (pintype "passive"))
    )
    (net (code "82") (name "unconnected-(SV2-Pad6)") (class "Default")
      (node (ref "SV2") (pin "6") (pinfunction "6_6") (pintype "passive"))
    )
  )
)
